# Ink-Schematic.net
KiCad netlist of a schematic drawn in EAGLE
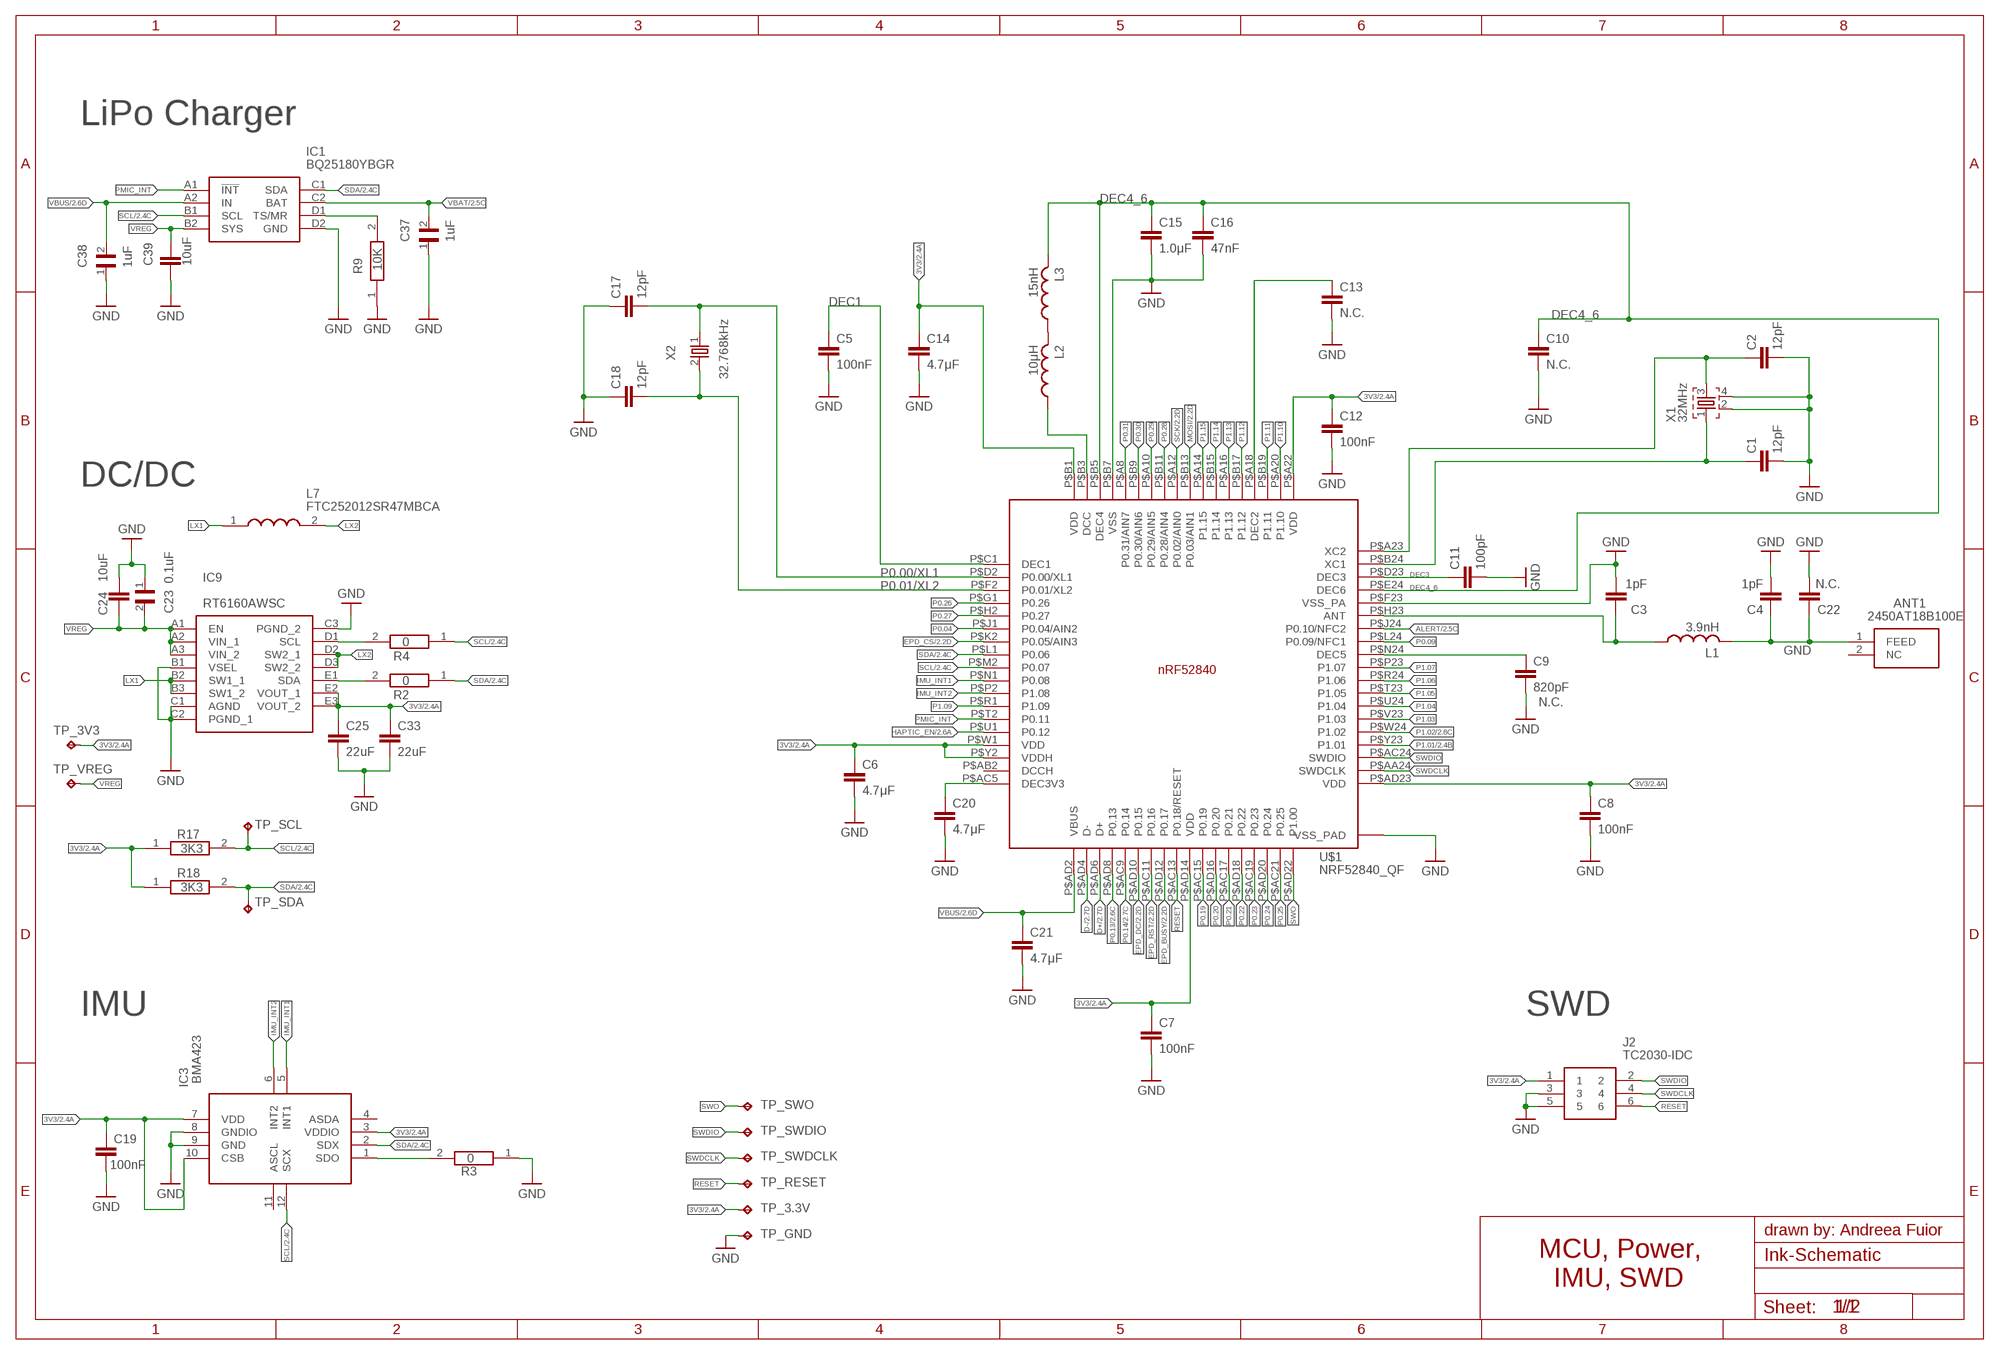
[diagram p0: schematic, sheet 1, part 1 of 2]
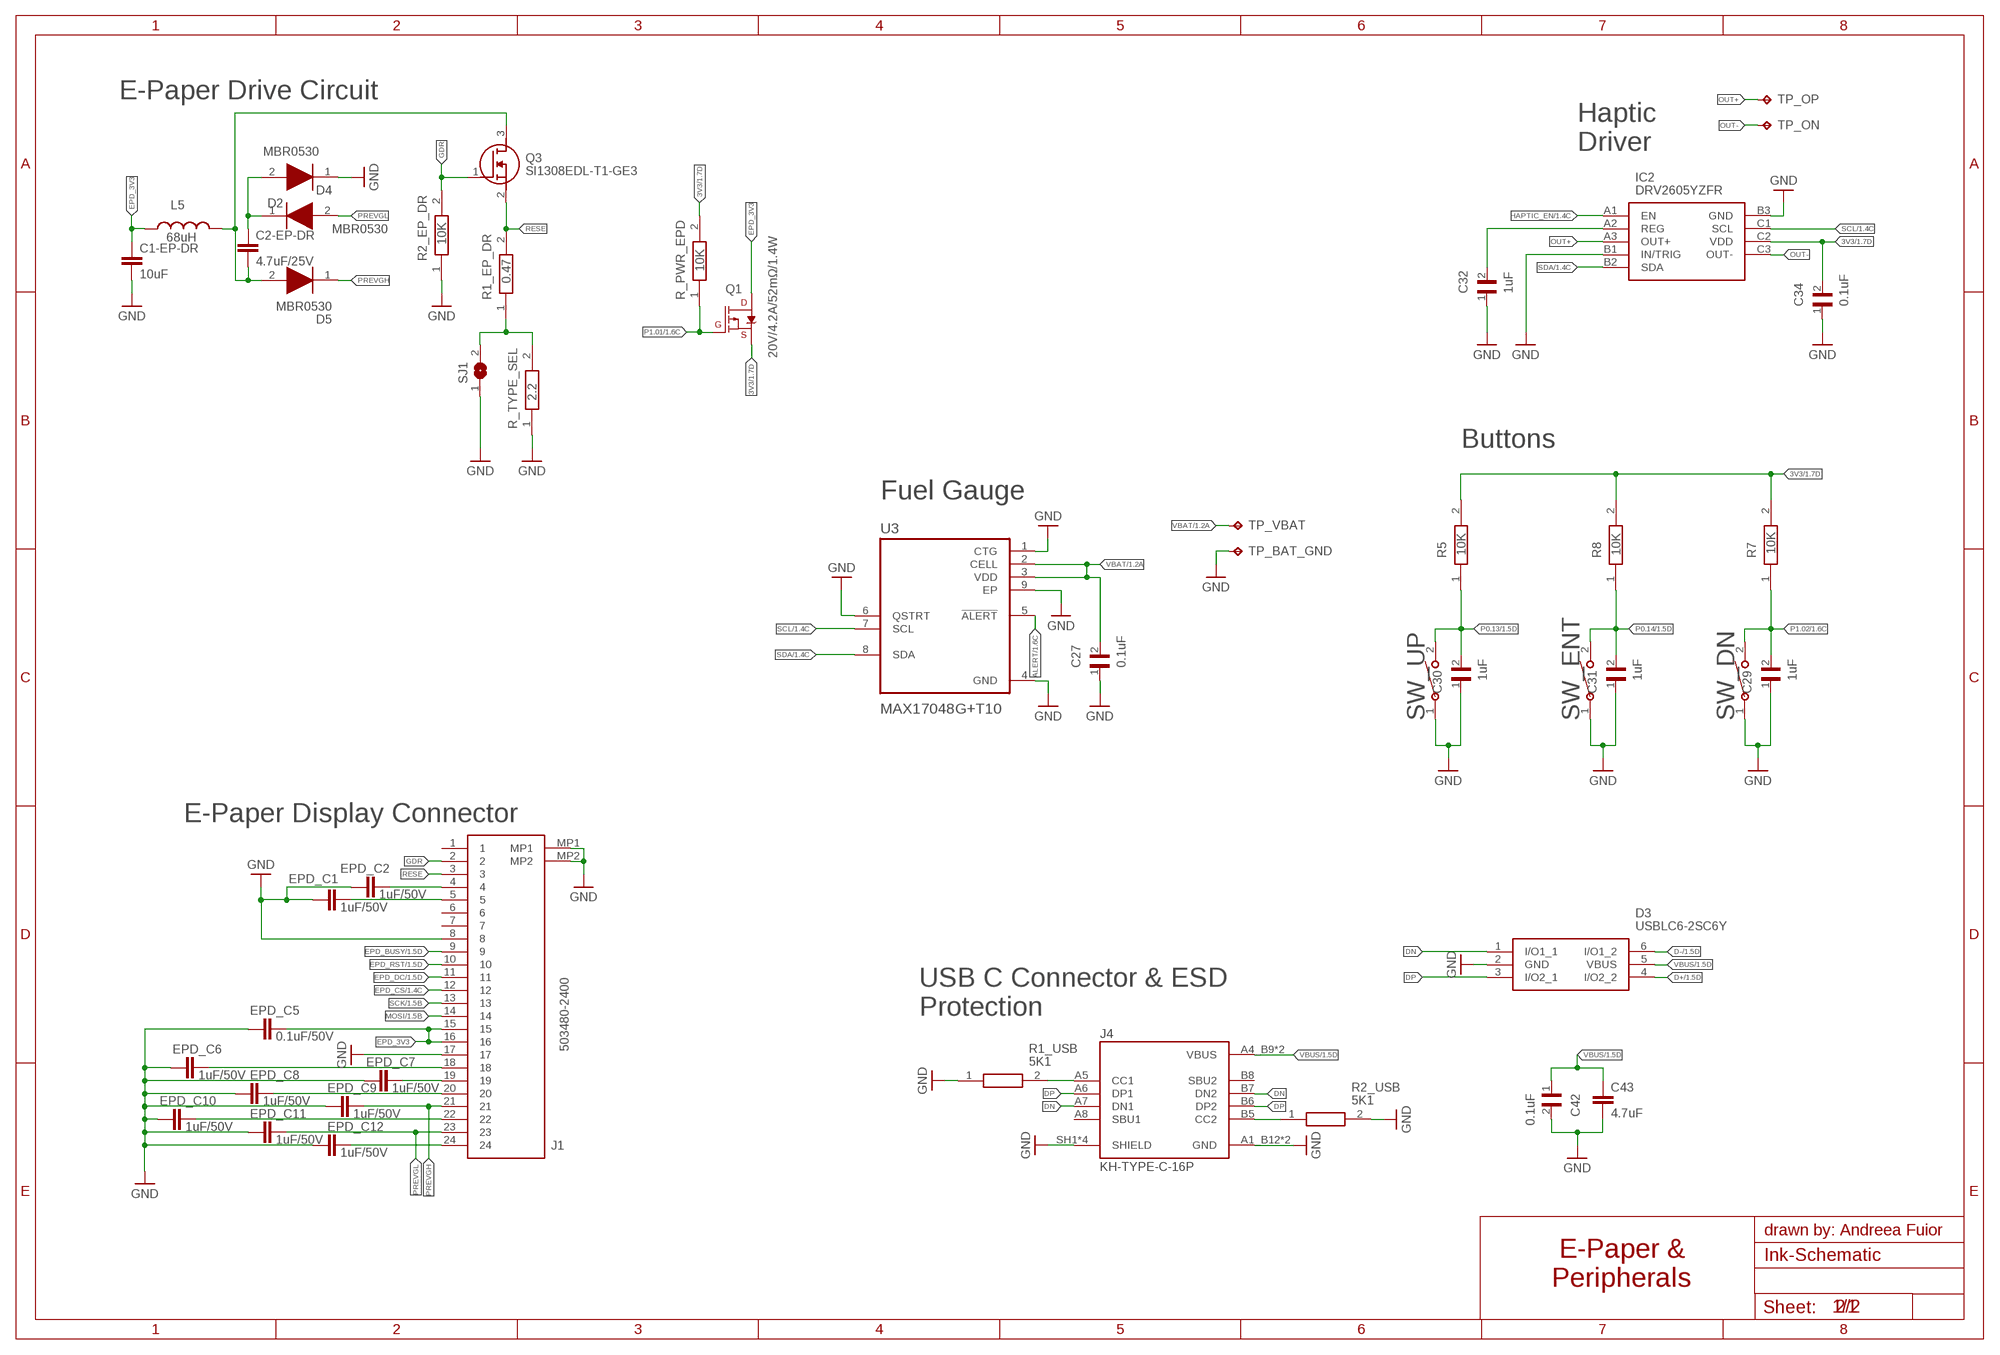
[diagram p1: schematic, sheet 1, part 2 of 2]

(export (version "E")
  (design (tool "Eeschema 10.0.6"))
  (components
    (comp (ref "ANT1")
      (value "2450AT18B100E")
      (footprint "eagle-import:2450AT18B100E_ANTC3216X140N")
      (fields (field (name "MOUSER_PART_NUMBER") "609-2450AT18B100E"))
      (libsource (lib "eagle-import") (part "2450AT18B100E_2450AT18B100E"))
    )
    (comp (ref "C1")
      (value "12pF")
      (footprint "eagle-import:NORDIC_NRF_3_RESC0201_L")
      (libsource (lib "eagle-import") (part "NORDIC_NRF_3_CAPACITOR_0201_L"))
    )
    (comp (ref "C1-EP-DR")
      (value "10uF")
      (footprint "eagle-import:NORDIC_NRF_3_RESC0402_L")
      (libsource (lib "eagle-import") (part "NORDIC_NRF_3_CAPACITOR_0402_L"))
    )
    (comp (ref "C2")
      (value "12pF")
      (footprint "eagle-import:NORDIC_NRF_3_RESC0201_L")
      (libsource (lib "eagle-import") (part "NORDIC_NRF_3_CAPACITOR_0201_L"))
    )
    (comp (ref "C2-EP-DR")
      (value "4.7uF/25V")
      (footprint "eagle-import:NORDIC_NRF_3_RESC0402_L")
      (libsource (lib "eagle-import") (part "NORDIC_NRF_3_CAPACITOR_0402_L"))
    )
    (comp (ref "C3")
      (value "1pF")
      (footprint "eagle-import:NORDIC_NRF_3_RESC0201_L")
      (libsource (lib "eagle-import") (part "NORDIC_NRF_3_CAPACITOR_0201_L"))
    )
    (comp (ref "C4")
      (value "1pF")
      (footprint "eagle-import:NORDIC_NRF_3_RESC0201_L")
      (libsource (lib "eagle-import") (part "NORDIC_NRF_3_CAPACITOR_0201_L"))
    )
    (comp (ref "C5")
      (value "100nF")
      (footprint "eagle-import:NORDIC_NRF_3_RESC0201_L")
      (libsource (lib "eagle-import") (part "NORDIC_NRF_3_CAPACITOR_0201_L"))
    )
    (comp (ref "C6")
      (value "4.7μF")
      (footprint "eagle-import:NORDIC_NRF_3_RESC0402_L")
      (libsource (lib "eagle-import") (part "NORDIC_NRF_3_CAPACITOR_0402_L"))
    )
    (comp (ref "C7")
      (value "100nF")
      (footprint "eagle-import:NORDIC_NRF_3_RESC0201_L")
      (libsource (lib "eagle-import") (part "NORDIC_NRF_3_CAPACITOR_0201_L"))
    )
    (comp (ref "C8")
      (value "100nF")
      (footprint "eagle-import:NORDIC_NRF_3_RESC0201_L")
      (libsource (lib "eagle-import") (part "NORDIC_NRF_3_CAPACITOR_0201_L"))
    )
    (comp (ref "C9")
      (value "820pF")
      (footprint "eagle-import:NORDIC_NRF_3_RESC0201_L")
      (libsource (lib "eagle-import") (part "NORDIC_NRF_3_CAPACITOR_0201_L"))
    )
    (comp (ref "C10")
      (value "N.C.")
      (footprint "eagle-import:NORDIC_NRF_3_RESC0201_L")
      (libsource (lib "eagle-import") (part "NORDIC_NRF_3_CAPACITOR_0201_L"))
    )
    (comp (ref "C11")
      (value "100pF")
      (footprint "eagle-import:NORDIC_NRF_3_RESC0201_L")
      (libsource (lib "eagle-import") (part "NORDIC_NRF_3_CAPACITOR_0201_L"))
    )
    (comp (ref "C12")
      (value "100nF")
      (footprint "eagle-import:NORDIC_NRF_3_RESC0201_L")
      (libsource (lib "eagle-import") (part "NORDIC_NRF_3_CAPACITOR_0201_L"))
    )
    (comp (ref "C13")
      (value "N.C.")
      (footprint "eagle-import:NORDIC_NRF_3_RESC0201_L")
      (libsource (lib "eagle-import") (part "NORDIC_NRF_3_CAPACITOR_0201_L"))
    )
    (comp (ref "C14")
      (value "4.7μF")
      (footprint "eagle-import:NORDIC_NRF_3_RESC0402_L")
      (libsource (lib "eagle-import") (part "NORDIC_NRF_3_CAPACITOR_0402_L"))
    )
    (comp (ref "C15")
      (value "1.0μF")
      (footprint "eagle-import:NORDIC_NRF_3_RESC0402_L")
      (libsource (lib "eagle-import") (part "NORDIC_NRF_3_CAPACITOR_0402_L"))
    )
    (comp (ref "C16")
      (value "47nF")
      (footprint "eagle-import:NORDIC_NRF_3_RESC0201_L")
      (libsource (lib "eagle-import") (part "NORDIC_NRF_3_CAPACITOR_0201_L"))
    )
    (comp (ref "C17")
      (value "12pF")
      (footprint "eagle-import:NORDIC_NRF_3_RESC0201_L")
      (libsource (lib "eagle-import") (part "NORDIC_NRF_3_CAPACITOR_0201_L"))
    )
    (comp (ref "C18")
      (value "12pF")
      (footprint "eagle-import:NORDIC_NRF_3_RESC0201_L")
      (libsource (lib "eagle-import") (part "NORDIC_NRF_3_CAPACITOR_0201_L"))
    )
    (comp (ref "C19")
      (value "100nF")
      (footprint "eagle-import:NORDIC_NRF_3_RESC0201_L")
      (libsource (lib "eagle-import") (part "NORDIC_NRF_3_CAPACITOR_0201_L"))
    )
    (comp (ref "C20")
      (value "4.7μF")
      (footprint "eagle-import:NORDIC_NRF_3_RESC0402_L")
      (libsource (lib "eagle-import") (part "NORDIC_NRF_3_CAPACITOR_0402_L"))
    )
    (comp (ref "C21")
      (value "4.7μF")
      (footprint "eagle-import:NORDIC_NRF_3_RESC0402_L")
      (libsource (lib "eagle-import") (part "NORDIC_NRF_3_CAPACITOR_0402_L"))
    )
    (comp (ref "C22")
      (value "N.C.")
      (footprint "eagle-import:NORDIC_NRF_3_RESC0201_L")
      (libsource (lib "eagle-import") (part "NORDIC_NRF_3_CAPACITOR_0201_L"))
    )
    (comp (ref "C23")
      (value "0.1uF")
      (footprint "eagle-import:GRM011R60J152KE01L_2_CAPC0201X13N")
      (fields (field (name "MF") "Murata") (field (name "MP") "GRM011R60J152KE01L"))
      (libsource (lib "eagle-import") (part "GRM011R60J152KE01L_2_GRM011R60J152KE01L"))
    )
    (comp (ref "C24")
      (value "10uF")
      (footprint "eagle-import:NORDIC_NRF_3_RESC0402_L")
      (libsource (lib "eagle-import") (part "NORDIC_NRF_3_CAPACITOR_0402_L"))
    )
    (comp (ref "C25")
      (value "22uF")
      (footprint "eagle-import:NORDIC_NRF_3_RESC0402_L")
      (libsource (lib "eagle-import") (part "NORDIC_NRF_3_CAPACITOR_0402_L"))
    )
    (comp (ref "C27")
      (value "0.1uF")
      (footprint "eagle-import:GRM011R60J152KE01L_2_CAPC0201X13N")
      (fields (field (name "MF") "Murata") (field (name "MP") "GRM011R60J152KE01L"))
      (libsource (lib "eagle-import") (part "GRM011R60J152KE01L_2_GRM011R60J152KE01L"))
    )
    (comp (ref "C29")
      (value "1uF")
      (footprint "eagle-import:GRM011R60J152KE01L_2_CAPC0201X13N")
      (fields (field (name "MF") "Murata") (field (name "MP") "GRM011R60J152KE01L"))
      (libsource (lib "eagle-import") (part "GRM011R60J152KE01L_2_GRM011R60J152KE01L"))
    )
    (comp (ref "C30")
      (value "1uF")
      (footprint "eagle-import:GRM011R60J152KE01L_2_CAPC0201X13N")
      (fields (field (name "MF") "Murata") (field (name "MP") "GRM011R60J152KE01L"))
      (libsource (lib "eagle-import") (part "GRM011R60J152KE01L_2_GRM011R60J152KE01L"))
    )
    (comp (ref "C31")
      (value "1uF")
      (footprint "eagle-import:GRM011R60J152KE01L_2_CAPC0201X13N")
      (fields (field (name "MF") "Murata") (field (name "MP") "GRM011R60J152KE01L"))
      (libsource (lib "eagle-import") (part "GRM011R60J152KE01L_2_GRM011R60J152KE01L"))
    )
    (comp (ref "C32")
      (value "1uF")
      (footprint "eagle-import:GRM011R60J152KE01L_2_CAPC0201X13N")
      (fields (field (name "MF") "Murata") (field (name "MP") "GRM011R60J152KE01L"))
      (libsource (lib "eagle-import") (part "GRM011R60J152KE01L_2_GRM011R60J152KE01L"))
    )
    (comp (ref "C33")
      (value "22uF")
      (footprint "eagle-import:NORDIC_NRF_3_RESC0402_L")
      (libsource (lib "eagle-import") (part "NORDIC_NRF_3_CAPACITOR_0402_L"))
    )
    (comp (ref "C34")
      (value "0.1uF")
      (footprint "eagle-import:GRM011R60J152KE01L_2_CAPC0201X13N")
      (fields (field (name "MF") "Murata") (field (name "MP") "GRM011R60J152KE01L"))
      (libsource (lib "eagle-import") (part "GRM011R60J152KE01L_2_GRM011R60J152KE01L"))
    )
    (comp (ref "C37")
      (value "1uF")
      (footprint "eagle-import:GRM011R60J152KE01L_2_CAPC0201X13N")
      (fields (field (name "MF") "Murata") (field (name "MP") "GRM011R60J152KE01L"))
      (libsource (lib "eagle-import") (part "GRM011R60J152KE01L_2_GRM011R60J152KE01L"))
    )
    (comp (ref "C38")
      (value "1uF")
      (footprint "eagle-import:GRM011R60J152KE01L_2_CAPC0201X13N")
      (fields (field (name "MF") "Murata") (field (name "MP") "GRM011R60J152KE01L"))
      (libsource (lib "eagle-import") (part "GRM011R60J152KE01L_2_GRM011R60J152KE01L"))
    )
    (comp (ref "C39")
      (value "10uF")
      (footprint "eagle-import:NORDIC_NRF_3_RESC0402_L")
      (libsource (lib "eagle-import") (part "NORDIC_NRF_3_CAPACITOR_0402_L"))
    )
    (comp (ref "C42")
      (value "0.1uF")
      (footprint "eagle-import:GRM011R60J152KE01L_2_CAPC0201X13N")
      (fields (field (name "MF") "Murata") (field (name "MP") "GRM011R60J152KE01L"))
      (libsource (lib "eagle-import") (part "GRM011R60J152KE01L_2_GRM011R60J152KE01L"))
    )
    (comp (ref "C43")
      (value "4.7uF")
      (footprint "eagle-import:NORDIC_NRF_3_RESC0402_L")
      (libsource (lib "eagle-import") (part "NORDIC_NRF_3_CAPACITOR_0402_L"))
    )
    (comp (ref "D2")
      (value "MBR0530")
      (footprint "eagle-import:ESP32_C6_LIBRARY_5_SOD3716X135N")
      (fields (field (name "MF") "ON Semiconductor"))
      (libsource (lib "eagle-import") (part "ESP32_C6_LIBRARY_5_MBR0530"))
    )
    (comp (ref "D3")
      (value "USBLC6-2SC6Y")
      (footprint "eagle-import:ESP32_C6_LIBRARY_3_SOT95P280X145-6N")
      (fields (field (name "MF") "STMicroelectronics"))
      (libsource (lib "eagle-import") (part "ESP32_C6_LIBRARY_3_USBLC6-2SC6Y"))
    )
    (comp (ref "D4")
      (value "MBR0530")
      (footprint "eagle-import:ESP32_C6_LIBRARY_5_SOD3716X135N")
      (fields (field (name "MF") "ON Semiconductor"))
      (libsource (lib "eagle-import") (part "ESP32_C6_LIBRARY_5_MBR0530"))
    )
    (comp (ref "D5")
      (value "MBR0530")
      (footprint "eagle-import:ESP32_C6_LIBRARY_5_SOD3716X135N")
      (fields (field (name "MF") "ON Semiconductor"))
      (libsource (lib "eagle-import") (part "ESP32_C6_LIBRARY_5_MBR0530"))
    )
    (comp (ref "EPD_C1")
      (value "1uF/50V")
      (footprint "eagle-import:NORDIC_NRF_3_RESC0402_L")
      (libsource (lib "eagle-import") (part "NORDIC_NRF_3_CAPACITOR_0402_L"))
    )
    (comp (ref "EPD_C2")
      (value "1uF/50V")
      (footprint "eagle-import:NORDIC_NRF_3_RESC0402_L")
      (libsource (lib "eagle-import") (part "NORDIC_NRF_3_CAPACITOR_0402_L"))
    )
    (comp (ref "EPD_C5")
      (value "0.1uF/50V")
      (footprint "eagle-import:NORDIC_NRF_3_RESC0402_L")
      (libsource (lib "eagle-import") (part "NORDIC_NRF_3_CAPACITOR_0402_L"))
    )
    (comp (ref "EPD_C6")
      (value "1uF/50V")
      (footprint "eagle-import:NORDIC_NRF_3_RESC0402_L")
      (libsource (lib "eagle-import") (part "NORDIC_NRF_3_CAPACITOR_0402_L"))
    )
    (comp (ref "EPD_C7")
      (value "1uF/50V")
      (footprint "eagle-import:NORDIC_NRF_3_RESC0402_L")
      (libsource (lib "eagle-import") (part "NORDIC_NRF_3_CAPACITOR_0402_L"))
    )
    (comp (ref "EPD_C8")
      (value "1uF/50V")
      (footprint "eagle-import:NORDIC_NRF_3_RESC0402_L")
      (libsource (lib "eagle-import") (part "NORDIC_NRF_3_CAPACITOR_0402_L"))
    )
    (comp (ref "EPD_C9")
      (value "1uF/50V")
      (footprint "eagle-import:NORDIC_NRF_3_RESC0402_L")
      (libsource (lib "eagle-import") (part "NORDIC_NRF_3_CAPACITOR_0402_L"))
    )
    (comp (ref "EPD_C10")
      (value "1uF/50V")
      (footprint "eagle-import:NORDIC_NRF_3_RESC0402_L")
      (libsource (lib "eagle-import") (part "NORDIC_NRF_3_CAPACITOR_0402_L"))
    )
    (comp (ref "EPD_C11")
      (value "1uF/50V")
      (footprint "eagle-import:NORDIC_NRF_3_RESC0402_L")
      (libsource (lib "eagle-import") (part "NORDIC_NRF_3_CAPACITOR_0402_L"))
    )
    (comp (ref "EPD_C12")
      (value "1uF/50V")
      (footprint "eagle-import:NORDIC_NRF_3_RESC0402_L")
      (libsource (lib "eagle-import") (part "NORDIC_NRF_3_CAPACITOR_0402_L"))
    )
    (comp (ref "IC1")
      (value "BQ25180YBGR")
      (footprint "eagle-import:BQ25180YBGR_BGA8C40P2X4_100X155X50")
      (fields (field (name "MOUSER_PART_NUMBER") "595-BQ25180YBGR"))
      (libsource (lib "eagle-import") (part "BQ25180YBGR_BQ25180YBGR"))
    )
    (comp (ref "IC2")
      (value "DRV2605YZFR")
      (footprint "eagle-import:DRV2605YZFR_BGA9C50P3X3_144X144X62")
      (libsource (lib "eagle-import") (part "DRV2605YZFR_DRV2605YZFR"))
    )
    (comp (ref "IC3")
      (value "BMA423")
      (footprint "eagle-import:BMA423_BMA423")
      (fields (field (name "MOUSER_PART_NUMBER") "262-BMA423"))
      (libsource (lib "eagle-import") (part "BMA423_BMA423"))
    )
    (comp (ref "IC9")
      (value "RT6160AWSC")
      (footprint "eagle-import:RT6160AWSC_BGA15C40P3X5_140X230X60")
      (fields (field (name "MOUSER_PART_NUMBER") "835-RT6160AWSC"))
      (libsource (lib "eagle-import") (part "RT6160AWSC_RT6160AWSC"))
    )
    (comp (ref "J1")
      (value "503480-2400")
      (footprint "eagle-import:503480-2400_5034802400")
      (fields (field (name "MOUSER_PART_NUMBER") "538-503480-2400"))
      (libsource (lib "eagle-import") (part "503480-2400_503480-2400"))
    )
    (comp (ref "J2")
      (value "TC2030-IDC")
      (footprint "eagle-import:TC2030-IDC_TC2030IDC")
      (libsource (lib "eagle-import") (part "TC2030-IDC_TC2030-IDC"))
    )
    (comp (ref "J4")
      (value "KH-TYPE-C-16P")
      (footprint "eagle-import:KH-TYPE-C-16P_KINGHELM_KH-TYPE-C-16P")
      (fields (field (name "MF") "kinghelm"))
      (libsource (lib "eagle-import") (part "KH-TYPE-C-16P_KH-TYPE-C-16P"))
    )
    (comp (ref "L1")
      (value "3.9nH")
      (footprint "eagle-import:NORDIC_NRF_2_RESC0402_L")
      (libsource (lib "eagle-import") (part "NORDIC_NRF_2_INDUCTOR_0402_L"))
    )
    (comp (ref "L2")
      (value "10μH")
      (footprint "eagle-import:NORDIC_NRF_2_RESC0402_L")
      (libsource (lib "eagle-import") (part "NORDIC_NRF_2_INDUCTOR_0402_L"))
    )
    (comp (ref "L3")
      (value "15nH")
      (footprint "eagle-import:NORDIC_NRF_2_RESC0402_L")
      (libsource (lib "eagle-import") (part "NORDIC_NRF_2_INDUCTOR_0402_L"))
    )
    (comp (ref "L5")
      (value "68uH")
      (footprint "eagle-import:NORDIC_NRF_2_RESC0402_L")
      (libsource (lib "eagle-import") (part "NORDIC_NRF_2_INDUCTOR_0402_L"))
    )
    (comp (ref "L7")
      (value "FTC252012SR47MBCA")
      (footprint "eagle-import:MLP2016SR47MT0S1_INDC2016X100N")
      (libsource (lib "eagle-import") (part "MLP2016SR47MT0S1_FTC252012SR47MBCA"))
    )
    (comp (ref "Q1")
      (value "20V/4.2A/52mΩ/1.4W")
      (footprint "eagle-import:ESP32_C6_LIBRARY_4_ESP32_C6_LIBRARY_4_ESP32_C6_LIBRARY_4_ESP32_C6_LIBRARY_4_ESP32_WROVER_SPARKFUN-DISCRETESEMI_SOT23-3")
      (libsource (lib "eagle-import") (part "ESP32_C6_LIBRARY_4_ESP32_WROVER_SPARKFUN-DISCRETESEMI_MOSFET_PCH-DMG2305UX-7"))
    )
    (comp (ref "Q3")
      (value "SI1308EDL-T1-GE3")
      (footprint "eagle-import:ESP32_C6_LIBRARY_6_SOT65P210X110-3N")
      (fields (field (name "MF") "Vishay Siliconix"))
      (libsource (lib "eagle-import") (part "ESP32_C6_LIBRARY_6_SI1308EDL-T1-GE3"))
    )
    (comp (ref "R1_EP_DR")
      (value "0.47")
      (footprint "eagle-import:CPF0201D7K68C1_0201")
      (libsource (lib "eagle-import") (part "CPF0201D7K68C1_CPF0201D7K68C1"))
    )
    (comp (ref "R1_USB")
      (value "5K1")
      (footprint "eagle-import:CPF0201D7K68C1_0201")
      (libsource (lib "eagle-import") (part "CPF0201D7K68C1_CPF0201D7K68C1"))
    )
    (comp (ref "R2")
      (value "0")
      (footprint "eagle-import:CPF0201D7K68C1_0201")
      (libsource (lib "eagle-import") (part "CPF0201D7K68C1_CPF0201D7K68C1"))
    )
    (comp (ref "R2_EP_DR")
      (value "10K")
      (footprint "eagle-import:CPF0201D7K68C1_0201")
      (libsource (lib "eagle-import") (part "CPF0201D7K68C1_CPF0201D7K68C1"))
    )
    (comp (ref "R2_USB")
      (value "5K1")
      (footprint "eagle-import:CPF0201D7K68C1_0201")
      (libsource (lib "eagle-import") (part "CPF0201D7K68C1_CPF0201D7K68C1"))
    )
    (comp (ref "R3")
      (value "0")
      (footprint "eagle-import:CPF0201D7K68C1_0201")
      (libsource (lib "eagle-import") (part "CPF0201D7K68C1_CPF0201D7K68C1"))
    )
    (comp (ref "R4")
      (value "0")
      (footprint "eagle-import:CPF0201D7K68C1_0201")
      (libsource (lib "eagle-import") (part "CPF0201D7K68C1_CPF0201D7K68C1"))
    )
    (comp (ref "R5")
      (value "10K")
      (footprint "eagle-import:CPF0201D7K68C1_0201")
      (libsource (lib "eagle-import") (part "CPF0201D7K68C1_CPF0201D7K68C1"))
    )
    (comp (ref "R7")
      (value "10K")
      (footprint "eagle-import:CPF0201D7K68C1_0201")
      (libsource (lib "eagle-import") (part "CPF0201D7K68C1_CPF0201D7K68C1"))
    )
    (comp (ref "R8")
      (value "10K")
      (footprint "eagle-import:CPF0201D7K68C1_0201")
      (libsource (lib "eagle-import") (part "CPF0201D7K68C1_CPF0201D7K68C1"))
    )
    (comp (ref "R9")
      (value "10K")
      (footprint "eagle-import:CPF0201D7K68C1_0201")
      (libsource (lib "eagle-import") (part "CPF0201D7K68C1_CPF0201D7K68C1"))
    )
    (comp (ref "R17")
      (value "3K3")
      (footprint "eagle-import:CPF0201D7K68C1_0201")
      (libsource (lib "eagle-import") (part "CPF0201D7K68C1_CPF0201D7K68C1"))
    )
    (comp (ref "R18")
      (value "3K3")
      (footprint "eagle-import:CPF0201D7K68C1_0201")
      (libsource (lib "eagle-import") (part "CPF0201D7K68C1_CPF0201D7K68C1"))
    )
    (comp (ref "R_PWR_EPD")
      (value "10K")
      (footprint "eagle-import:CPF0201D7K68C1_0201")
      (libsource (lib "eagle-import") (part "CPF0201D7K68C1_CPF0201D7K68C1"))
    )
    (comp (ref "R_TYPE_SEL")
      (value "2.2")
      (footprint "eagle-import:CPF0201D7K68C1_0201")
      (libsource (lib "eagle-import") (part "CPF0201D7K68C1_CPF0201D7K68C1"))
    )
    (comp (ref "SJ1")
      (value "ESP32_C6_LIBRARY_7_JUMPER_SJ")
      (footprint "eagle-import:ESP32_C6_LIBRARY_7_JUMPER_SJ")
      (libsource (lib "eagle-import") (part "ESP32_C6_LIBRARY_7_JUMPER_SJ"))
    )
    (comp (ref "SW_DN")
      (value "2025-10-22_07-23-44_LIBRARY_EVP-AKE31ASW_EVP-AKE31A_PAN")
      (footprint "eagle-import:2025-10-22_07-23-44_LIBRARY_SW_EVP-AKE31A_PAN")
      (fields
        (field (name "MANUFACTURER_PART_NUMBER") "EVP-AKE31A")
        (field (name "COPYRIGHT") "Copyright (C) 2025 Ultra Librarian. All rights reserved.")
      )
      (libsource (lib "eagle-import") (part "2025-10-22_07-23-44_LIBRARY_EVP-AKE31ASW_EVP-AKE31A_PAN"))
    )
    (comp (ref "SW_ENT")
      (value "2025-10-22_07-23-44_LIBRARY_EVP-AKE31ASW_EVP-AKE31A_PAN")
      (footprint "eagle-import:2025-10-22_07-23-44_LIBRARY_SW_EVP-AKE31A_PAN")
      (fields
        (field (name "MANUFACTURER_PART_NUMBER") "EVP-AKE31A")
        (field (name "COPYRIGHT") "Copyright (C) 2025 Ultra Librarian. All rights reserved.")
      )
      (libsource (lib "eagle-import") (part "2025-10-22_07-23-44_LIBRARY_EVP-AKE31ASW_EVP-AKE31A_PAN"))
    )
    (comp (ref "SW_UP")
      (value "2025-10-22_07-23-44_LIBRARY_EVP-AKE31ASW_EVP-AKE31A_PAN")
      (footprint "eagle-import:2025-10-22_07-23-44_LIBRARY_SW_EVP-AKE31A_PAN")
      (fields
        (field (name "MANUFACTURER_PART_NUMBER") "EVP-AKE31A")
        (field (name "COPYRIGHT") "Copyright (C) 2025 Ultra Librarian. All rights reserved.")
      )
      (libsource (lib "eagle-import") (part "2025-10-22_07-23-44_LIBRARY_EVP-AKE31ASW_EVP-AKE31A_PAN"))
    )
    (comp (ref "TP_3.3V")
      (value "HECTOR_WATCH_1_TPTP20R")
      (footprint "eagle-import:HECTOR_WATCH_1_TP20R")
      (libsource (lib "eagle-import") (part "HECTOR_WATCH_1_TPTP20R"))
    )
    (comp (ref "TP_3V3")
      (value "HECTOR_WATCH_1_TPTP20R")
      (footprint "eagle-import:HECTOR_WATCH_1_TP20R")
      (libsource (lib "eagle-import") (part "HECTOR_WATCH_1_TPTP20R"))
    )
    (comp (ref "TP_BAT_GND")
      (value "HECTOR_WATCH_1_TPTP20R")
      (footprint "eagle-import:HECTOR_WATCH_1_TP20R")
      (libsource (lib "eagle-import") (part "HECTOR_WATCH_1_TPTP20R"))
    )
    (comp (ref "TP_GND")
      (value "HECTOR_WATCH_1_TPTP20R")
      (footprint "eagle-import:HECTOR_WATCH_1_TP20R")
      (libsource (lib "eagle-import") (part "HECTOR_WATCH_1_TPTP20R"))
    )
    (comp (ref "TP_ON")
      (value "HECTOR_WATCH_1_TPTP20R")
      (footprint "eagle-import:HECTOR_WATCH_1_TP20R")
      (libsource (lib "eagle-import") (part "HECTOR_WATCH_1_TPTP20R"))
    )
    (comp (ref "TP_OP")
      (value "HECTOR_WATCH_1_TPTP20R")
      (footprint "eagle-import:HECTOR_WATCH_1_TP20R")
      (libsource (lib "eagle-import") (part "HECTOR_WATCH_1_TPTP20R"))
    )
    (comp (ref "TP_RESET")
      (value "HECTOR_WATCH_1_TPTP20R")
      (footprint "eagle-import:HECTOR_WATCH_1_TP20R")
      (libsource (lib "eagle-import") (part "HECTOR_WATCH_1_TPTP20R"))
    )
    (comp (ref "TP_SCL")
      (value "HECTOR_WATCH_1_TPTP20R")
      (footprint "eagle-import:HECTOR_WATCH_1_TP20R")
      (libsource (lib "eagle-import") (part "HECTOR_WATCH_1_TPTP20R"))
    )
    (comp (ref "TP_SDA")
      (value "HECTOR_WATCH_1_TPTP20R")
      (footprint "eagle-import:HECTOR_WATCH_1_TP20R")
      (libsource (lib "eagle-import") (part "HECTOR_WATCH_1_TPTP20R"))
    )
    (comp (ref "TP_SWDCLK")
      (value "HECTOR_WATCH_1_TPTP20R")
      (footprint "eagle-import:HECTOR_WATCH_1_TP20R")
      (libsource (lib "eagle-import") (part "HECTOR_WATCH_1_TPTP20R"))
    )
    (comp (ref "TP_SWDIO")
      (value "HECTOR_WATCH_1_TPTP20R")
      (footprint "eagle-import:HECTOR_WATCH_1_TP20R")
      (libsource (lib "eagle-import") (part "HECTOR_WATCH_1_TPTP20R"))
    )
    (comp (ref "TP_SWO")
      (value "HECTOR_WATCH_1_TPTP20R")
      (footprint "eagle-import:HECTOR_WATCH_1_TP20R")
      (libsource (lib "eagle-import") (part "HECTOR_WATCH_1_TPTP20R"))
    )
    (comp (ref "TP_VBAT")
      (value "HECTOR_WATCH_1_TPTP20R")
      (footprint "eagle-import:HECTOR_WATCH_1_TP20R")
      (libsource (lib "eagle-import") (part "HECTOR_WATCH_1_TPTP20R"))
    )
    (comp (ref "TP_VREG")
      (value "HECTOR_WATCH_1_TPTP20R")
      (footprint "eagle-import:HECTOR_WATCH_1_TP20R")
      (libsource (lib "eagle-import") (part "HECTOR_WATCH_1_TPTP20R"))
    )
    (comp (ref "U$1")
      (value "NRF52840_QF")
      (footprint "eagle-import:NORDIC_NRF_4_AQFN50P700X700X85_HS-74N")
      (libsource (lib "eagle-import") (part "NORDIC_NRF_4_NRF52840_QF"))
    )
    (comp (ref "U3")
      (value "MAX17048G+T10")
      (footprint "eagle-import:ESP32_C6_LIBRARY_SON50P200X200X80-9N")
      (fields (field (name "MF") "Analog Devices"))
      (libsource (lib "eagle-import") (part "ESP32_C6_LIBRARY_MAX17048G+T10"))
    )
    (comp (ref "X1")
      (value "32MHz")
      (footprint "eagle-import:NORDIC_NRF_BT-XTAL_2016_N")
      (libsource (lib "eagle-import") (part "NORDIC_NRF_XTAL_32MHZ"))
    )
    (comp (ref "X2")
      (value "32.768kHz")
      (footprint "eagle-import:NORDIC_NRF_1_XTAL_3215_N")
      (libsource (lib "eagle-import") (part "NORDIC_NRF_1_XTAL_32KHZ"))
    )
  )
  (nets
    (net (code "1") (name "/DEC1") (class "Default")
      (node (ref "C5") (pin "1") (pinfunction "1_1") (pintype "passive"))
      (node (ref "U$1") (pin "P$C1") (pinfunction "DEC1_P$C1") (pintype "power_in"))
    )
    (net (code "2") (name "/DEC3") (class "Default")
      (node (ref "C11") (pin "1") (pinfunction "1_1") (pintype "passive"))
      (node (ref "U$1") (pin "P$D23") (pinfunction "DEC3_P$D23") (pintype "bidirectional"))
    )
    (net (code "3") (name "/DEC4_6") (class "Default")
      (node (ref "C10") (pin "1") (pinfunction "1_1") (pintype "passive"))
      (node (ref "C15") (pin "1") (pinfunction "1_1") (pintype "passive"))
      (node (ref "C16") (pin "1") (pinfunction "1_1") (pintype "passive"))
      (node (ref "L3") (pin "2") (pinfunction "2_2") (pintype "passive"))
      (node (ref "U$1") (pin "P$B5") (pinfunction "DEC4_P$B5") (pintype "power_in"))
      (node (ref "U$1") (pin "P$E24") (pinfunction "DEC6_P$E24") (pintype "bidirectional"))
    )
    (net (code "4") (name "/P0.00{slash}XL1") (class "Default")
      (node (ref "C17") (pin "2") (pinfunction "2_2") (pintype "passive"))
      (node (ref "U$1") (pin "P$D2") (pinfunction "P0.00/XL1_P$D2") (pintype "bidirectional"))
      (node (ref "X2") (pin "1") (pinfunction "1_1") (pintype "passive"))
    )
    (net (code "5") (name "/P0.01{slash}XL2") (class "Default")
      (node (ref "C18") (pin "2") (pinfunction "2_2") (pintype "passive"))
      (node (ref "U$1") (pin "P$F2") (pinfunction "P0.01/XL2_P$F2") (pintype "bidirectional"))
      (node (ref "X2") (pin "2") (pinfunction "2_2") (pintype "passive"))
    )
    (net (code "6") (name "3V3{slash}1.7D") (class "Default")
      (node (ref "C34") (pin "2") (pinfunction "2_2") (pintype "passive"))
      (node (ref "IC2") (pin "C2") (pinfunction "VDD_C2") (pintype "bidirectional"))
      (node (ref "Q1") (pin "2") (pinfunction "S_2") (pintype "bidirectional"))
      (node (ref "R5") (pin "2") (pinfunction "2_2") (pintype "bidirectional"))
      (node (ref "R7") (pin "2") (pinfunction "2_2") (pintype "bidirectional"))
      (node (ref "R8") (pin "2") (pinfunction "2_2") (pintype "bidirectional"))
      (node (ref "R_PWR_EPD") (pin "2") (pinfunction "2_2") (pintype "bidirectional"))
    )
    (net (code "7") (name "3V3{slash}2.4A") (class "Default")
      (node (ref "C12") (pin "1") (pinfunction "1_1") (pintype "passive"))
      (node (ref "C14") (pin "1") (pinfunction "1_1") (pintype "passive"))
      (node (ref "C19") (pin "1") (pinfunction "1_1") (pintype "passive"))
      (node (ref "C25") (pin "1") (pinfunction "1_1") (pintype "passive"))
      (node (ref "C33") (pin "1") (pinfunction "1_1") (pintype "passive"))
      (node (ref "C6") (pin "1") (pinfunction "1_1") (pintype "passive"))
      (node (ref "C7") (pin "1") (pinfunction "1_1") (pintype "passive"))
      (node (ref "C8") (pin "1") (pinfunction "1_1") (pintype "passive"))
      (node (ref "IC3") (pin "10") (pinfunction "CSB_10") (pintype "bidirectional"))
      (node (ref "IC3") (pin "3") (pinfunction "VDDIO_3") (pintype "bidirectional"))
      (node (ref "IC3") (pin "7") (pinfunction "VDD_7") (pintype "bidirectional"))
      (node (ref "IC9") (pin "E2") (pinfunction "VOUT_1_E2") (pintype "bidirectional"))
      (node (ref "IC9") (pin "E3") (pinfunction "VOUT_2_E3") (pintype "bidirectional"))
      (node (ref "J2") (pin "1") (pinfunction "1_1") (pintype "bidirectional"))
      (node (ref "R17") (pin "1") (pinfunction "1_1") (pintype "bidirectional"))
      (node (ref "R18") (pin "1") (pinfunction "1_1") (pintype "bidirectional"))
      (node (ref "TP_3.3V") (pin "TP") (pinfunction "TP_TP") (pintype "input"))
      (node (ref "TP_3V3") (pin "TP") (pinfunction "TP_TP") (pintype "input"))
      (node (ref "U$1") (pin "P$A22") (pinfunction "VDD_P$A22") (pintype "power_in"))
      (node (ref "U$1") (pin "P$AD14") (pinfunction "VDD_P$AD14") (pintype "power_in"))
      (node (ref "U$1") (pin "P$AD23") (pinfunction "VDD_P$AD23") (pintype "power_in"))
      (node (ref "U$1") (pin "P$B1") (pinfunction "VDD_P$B1") (pintype "power_in"))
      (node (ref "U$1") (pin "P$W1") (pinfunction "VDD_P$W1") (pintype "power_in"))
      (node (ref "U$1") (pin "P$Y2") (pinfunction "VDDH_P$Y2") (pintype "power_in"))
    )
    (net (code "8") (name "ALERT{slash}1.6C") (class "Default")
      (node (ref "U3") (pin "5") (pinfunction "~{ALERT}_5") (pintype "output"))
    )
    (net (code "9") (name "ALERT{slash}2.5C") (class "Default")
      (node (ref "U$1") (pin "P$J24") (pinfunction "P0.10/NFC2_P$J24") (pintype "bidirectional"))
    )
    (net (code "10") (name "D+{slash}1.5D") (class "Default")
      (node (ref "D3") (pin "4") (pinfunction "I/O2_2_4") (pintype "bidirectional"))
    )
    (net (code "11") (name "D+{slash}2.7D") (class "Default")
      (node (ref "U$1") (pin "P$AD6") (pinfunction "D+_P$AD6") (pintype "bidirectional"))
    )
    (net (code "12") (name "D-{slash}1.5D") (class "Default")
      (node (ref "D3") (pin "6") (pinfunction "I/O1_2_6") (pintype "bidirectional"))
    )
    (net (code "13") (name "D-{slash}2.7D") (class "Default")
      (node (ref "U$1") (pin "P$AD4") (pinfunction "D-_P$AD4") (pintype "bidirectional"))
    )
    (net (code "14") (name "DN") (class "Default")
      (node (ref "D3") (pin "1") (pinfunction "I/O1_1_1") (pintype "bidirectional"))
      (node (ref "J4") (pin "A7") (pinfunction "DN1_A7") (pintype "bidirectional"))
      (node (ref "J4") (pin "B7") (pinfunction "DN2_B7") (pintype "bidirectional"))
    )
    (net (code "15") (name "DP") (class "Default")
      (node (ref "D3") (pin "3") (pinfunction "I/O2_1_3") (pintype "bidirectional"))
      (node (ref "J4") (pin "A6") (pinfunction "DP1_A6") (pintype "bidirectional"))
      (node (ref "J4") (pin "B6") (pinfunction "DP2_B6") (pintype "bidirectional"))
    )
    (net (code "16") (name "EPD_3V3") (class "Default")
      (node (ref "C1-EP-DR") (pin "1") (pinfunction "1_1") (pintype "passive"))
      (node (ref "EPD_C5") (pin "1") (pinfunction "1_1") (pintype "passive"))
      (node (ref "J1") (pin "15") (pinfunction "15_15") (pintype "bidirectional"))
      (node (ref "J1") (pin "16") (pinfunction "16_16") (pintype "bidirectional"))
      (node (ref "L5") (pin "1") (pinfunction "1_1") (pintype "passive"))
      (node (ref "Q1") (pin "3") (pinfunction "D_3") (pintype "bidirectional"))
    )
    (net (code "17") (name "EPD_BUSY{slash}1.5D") (class "Default")
      (node (ref "J1") (pin "9") (pinfunction "9_9") (pintype "bidirectional"))
    )
    (net (code "18") (name "EPD_BUSY{slash}2.2D") (class "Default")
      (node (ref "U$1") (pin "P$AD12") (pinfunction "P0.17_P$AD12") (pintype "bidirectional"))
    )
    (net (code "19") (name "EPD_CS{slash}1.4C") (class "Default")
      (node (ref "J1") (pin "12") (pinfunction "12_12") (pintype "bidirectional"))
    )
    (net (code "20") (name "EPD_CS{slash}2.2D") (class "Default")
      (node (ref "U$1") (pin "P$K2") (pinfunction "P0.05/AIN3_P$K2") (pintype "bidirectional"))
    )
    (net (code "21") (name "EPD_DC{slash}1.5D") (class "Default")
      (node (ref "J1") (pin "11") (pinfunction "11_11") (pintype "bidirectional"))
    )
    (net (code "22") (name "EPD_DC{slash}2.2D") (class "Default")
      (node (ref "U$1") (pin "P$AD10") (pinfunction "P0.15_P$AD10") (pintype "bidirectional"))
    )
    (net (code "23") (name "EPD_RST{slash}1.5D") (class "Default")
      (node (ref "J1") (pin "10") (pinfunction "10_10") (pintype "bidirectional"))
    )
    (net (code "24") (name "EPD_RST{slash}2.2D") (class "Default")
      (node (ref "U$1") (pin "P$AC11") (pinfunction "P0.16_P$AC11") (pintype "bidirectional"))
    )
    (net (code "25") (name "GDR") (class "Default")
      (node (ref "J1") (pin "2") (pinfunction "2_2") (pintype "bidirectional"))
      (node (ref "Q3") (pin "1") (pinfunction "G_1") (pintype "bidirectional"))
      (node (ref "R2_EP_DR") (pin "2") (pinfunction "2_2") (pintype "bidirectional"))
    )
    (net (code "26") (name "GND") (class "Default")
      (node (ref "ANT1") (pin "1") (pinfunction "FEED_1") (pintype "input"))
      (node (ref "C1") (pin "2") (pinfunction "2_2") (pintype "passive"))
      (node (ref "C1-EP-DR") (pin "2") (pinfunction "2_2") (pintype "passive"))
      (node (ref "C10") (pin "2") (pinfunction "2_2") (pintype "passive"))
      (node (ref "C11") (pin "2") (pinfunction "2_2") (pintype "passive"))
      (node (ref "C12") (pin "2") (pinfunction "2_2") (pintype "passive"))
      (node (ref "C13") (pin "2") (pinfunction "2_2") (pintype "passive"))
      (node (ref "C14") (pin "2") (pinfunction "2_2") (pintype "passive"))
      (node (ref "C15") (pin "2") (pinfunction "2_2") (pintype "passive"))
      (node (ref "C16") (pin "2") (pinfunction "2_2") (pintype "passive"))
      (node (ref "C17") (pin "1") (pinfunction "1_1") (pintype "passive"))
      (node (ref "C18") (pin "1") (pinfunction "1_1") (pintype "passive"))
      (node (ref "C19") (pin "2") (pinfunction "2_2") (pintype "passive"))
      (node (ref "C2") (pin "2") (pinfunction "2_2") (pintype "passive"))
      (node (ref "C20") (pin "2") (pinfunction "2_2") (pintype "passive"))
      (node (ref "C21") (pin "2") (pinfunction "2_2") (pintype "passive"))
      (node (ref "C22") (pin "1") (pinfunction "1_1") (pintype "passive"))
      (node (ref "C22") (pin "2") (pinfunction "2_2") (pintype "passive"))
      (node (ref "C23") (pin "1") (pinfunction "1_1") (pintype "passive"))
      (node (ref "C24") (pin "2") (pinfunction "2_2") (pintype "passive"))
      (node (ref "C25") (pin "2") (pinfunction "2_2") (pintype "passive"))
      (node (ref "C27") (pin "1") (pinfunction "1_1") (pintype "passive"))
      (node (ref "C29") (pin "1") (pinfunction "1_1") (pintype "passive"))
      (node (ref "C3") (pin "2") (pinfunction "2_2") (pintype "passive"))
      (node (ref "C30") (pin "1") (pinfunction "1_1") (pintype "passive"))
      (node (ref "C31") (pin "1") (pinfunction "1_1") (pintype "passive"))
      (node (ref "C32") (pin "1") (pinfunction "1_1") (pintype "passive"))
      (node (ref "C33") (pin "2") (pinfunction "2_2") (pintype "passive"))
      (node (ref "C34") (pin "1") (pinfunction "1_1") (pintype "passive"))
      (node (ref "C37") (pin "1") (pinfunction "1_1") (pintype "passive"))
      (node (ref "C38") (pin "1") (pinfunction "1_1") (pintype "passive"))
      (node (ref "C39") (pin "2") (pinfunction "2_2") (pintype "passive"))
      (node (ref "C4") (pin "1") (pinfunction "1_1") (pintype "passive"))
      (node (ref "C4") (pin "2") (pinfunction "2_2") (pintype "passive"))
      (node (ref "C42") (pin "2") (pinfunction "2_2") (pintype "passive"))
      (node (ref "C43") (pin "2") (pinfunction "2_2") (pintype "passive"))
      (node (ref "C5") (pin "2") (pinfunction "2_2") (pintype "passive"))
      (node (ref "C6") (pin "2") (pinfunction "2_2") (pintype "passive"))
      (node (ref "C7") (pin "2") (pinfunction "2_2") (pintype "passive"))
      (node (ref "C8") (pin "2") (pinfunction "2_2") (pintype "passive"))
      (node (ref "C9") (pin "2") (pinfunction "2_2") (pintype "passive"))
      (node (ref "D3") (pin "2") (pinfunction "GND_2") (pintype "bidirectional"))
      (node (ref "D4") (pin "1") (pinfunction "K_1") (pintype "bidirectional"))
      (node (ref "EPD_C1") (pin "2") (pinfunction "2_2") (pintype "passive"))
      (node (ref "EPD_C10") (pin "2") (pinfunction "2_2") (pintype "passive"))
      (node (ref "EPD_C11") (pin "2") (pinfunction "2_2") (pintype "passive"))
      (node (ref "EPD_C12") (pin "2") (pinfunction "2_2") (pintype "passive"))
      (node (ref "EPD_C2") (pin "2") (pinfunction "2_2") (pintype "passive"))
      (node (ref "EPD_C5") (pin "2") (pinfunction "2_2") (pintype "passive"))
      (node (ref "EPD_C6") (pin "2") (pinfunction "2_2") (pintype "passive"))
      (node (ref "EPD_C7") (pin "2") (pinfunction "2_2") (pintype "passive"))
      (node (ref "EPD_C8") (pin "2") (pinfunction "2_2") (pintype "passive"))
      (node (ref "EPD_C9") (pin "2") (pinfunction "2_2") (pintype "passive"))
      (node (ref "IC1") (pin "D2") (pinfunction "GND_D2") (pintype "bidirectional"))
      (node (ref "IC2") (pin "B1") (pinfunction "IN/TRIG_B1") (pintype "bidirectional"))
      (node (ref "IC2") (pin "B3") (pinfunction "GND_B3") (pintype "bidirectional"))
      (node (ref "IC3") (pin "8") (pinfunction "GNDIO_8") (pintype "bidirectional"))
      (node (ref "IC3") (pin "9") (pinfunction "GND_9") (pintype "bidirectional"))
      (node (ref "IC9") (pin "B1") (pinfunction "VSEL_B1") (pintype "bidirectional"))
      (node (ref "IC9") (pin "C1") (pinfunction "AGND_C1") (pintype "bidirectional"))
      (node (ref "IC9") (pin "C2") (pinfunction "PGND_1_C2") (pintype "bidirectional"))
      (node (ref "IC9") (pin "C3") (pinfunction "PGND_2_C3") (pintype "bidirectional"))
      (node (ref "J1") (pin "17") (pinfunction "17_17") (pintype "bidirectional"))
      (node (ref "J1") (pin "8") (pinfunction "8_8") (pintype "bidirectional"))
      (node (ref "J1") (pin "MP1") (pinfunction "MP1_MP1") (pintype "bidirectional"))
      (node (ref "J1") (pin "MP2") (pinfunction "MP2_MP2") (pintype "bidirectional"))
      (node (ref "J2") (pin "3") (pinfunction "3_3") (pintype "bidirectional"))
      (node (ref "J2") (pin "5") (pinfunction "5_5") (pintype "bidirectional"))
      (node (ref "J4") (pin "A12_B1") (pinfunction "GND_A12_B1") (pintype "power_in"))
      (node (ref "J4") (pin "A1_B12") (pinfunction "GND_A1_B12") (pintype "power_in"))
      (node (ref "J4") (pin "SH1") (pinfunction "SHIELD_SH1") (pintype "passive"))
      (node (ref "J4") (pin "SH2") (pinfunction "SHIELD_SH2") (pintype "passive"))
      (node (ref "J4") (pin "SH3") (pinfunction "SHIELD_SH3") (pintype "passive"))
      (node (ref "J4") (pin "SH4") (pinfunction "SHIELD_SH4") (pintype "passive"))
      (node (ref "L1") (pin "2") (pinfunction "2_2") (pintype "passive"))
      (node (ref "R1_USB") (pin "1") (pinfunction "1_1") (pintype "bidirectional"))
      (node (ref "R2_EP_DR") (pin "1") (pinfunction "1_1") (pintype "bidirectional"))
      (node (ref "R2_USB") (pin "2") (pinfunction "2_2") (pintype "bidirectional"))
      (node (ref "R3") (pin "1") (pinfunction "1_1") (pintype "bidirectional"))
      (node (ref "R9") (pin "1") (pinfunction "1_1") (pintype "bidirectional"))
      (node (ref "R_TYPE_SEL") (pin "1") (pinfunction "1_1") (pintype "bidirectional"))
      (node (ref "SJ1") (pin "1") (pinfunction "1_1") (pintype "passive"))
      (node (ref "SW_DN") (pin "1") (pinfunction "1_1") (pintype "passive"))
      (node (ref "SW_ENT") (pin "1") (pinfunction "1_1") (pintype "passive"))
      (node (ref "SW_UP") (pin "1") (pinfunction "1_1") (pintype "passive"))
      (node (ref "TP_BAT_GND") (pin "TP") (pinfunction "TP_TP") (pintype "input"))
      (node (ref "TP_GND") (pin "TP") (pinfunction "TP_TP") (pintype "input"))
      (node (ref "U$1") (pin "P$74") (pinfunction "VSS_PAD_P$74") (pintype "bidirectional"))
      (node (ref "U$1") (pin "P$75") (pinfunction "VSS_PAD_P$75") (pintype "bidirectional"))
      (node (ref "U$1") (pin "P$76") (pinfunction "VSS_PAD_P$76") (pintype "bidirectional"))
      (node (ref "U$1") (pin "P$77") (pinfunction "VSS_PAD_P$77") (pintype "bidirectional"))
      (node (ref "U$1") (pin "P$78") (pinfunction "VSS_PAD_P$78") (pintype "bidirectional"))
      (node (ref "U$1") (pin "P$79") (pinfunction "VSS_PAD_P$79") (pintype "bidirectional"))
      (node (ref "U$1") (pin "P$80") (pinfunction "VSS_PAD_P$80") (pintype "bidirectional"))
      (node (ref "U$1") (pin "P$81") (pinfunction "VSS_PAD_P$81") (pintype "bidirectional"))
      (node (ref "U$1") (pin "P$82") (pinfunction "VSS_PAD_P$82") (pintype "bidirectional"))
      (node (ref "U$1") (pin "P$83") (pinfunction "VSS_PAD_P$83") (pintype "bidirectional"))
      (node (ref "U$1") (pin "P$84") (pinfunction "VSS_PAD_P$84") (pintype "bidirectional"))
      (node (ref "U$1") (pin "P$85") (pinfunction "VSS_PAD_P$85") (pintype "bidirectional"))
      (node (ref "U$1") (pin "P$86") (pinfunction "VSS_PAD_P$86") (pintype "bidirectional"))
      (node (ref "U$1") (pin "P$87") (pinfunction "VSS_PAD_P$87") (pintype "bidirectional"))
      (node (ref "U$1") (pin "P$88") (pinfunction "VSS_PAD_P$88") (pintype "bidirectional"))
      (node (ref "U$1") (pin "P$89") (pinfunction "VSS_PAD_P$89") (pintype "bidirectional"))
      (node (ref "U$1") (pin "P$90") (pinfunction "VSS_PAD_P$90") (pintype "bidirectional"))
      (node (ref "U$1") (pin "P$B7") (pinfunction "VSS_P$B7") (pintype "power_in"))
      (node (ref "U$1") (pin "P$F23") (pinfunction "VSS_PA_P$F23") (pintype "bidirectional"))
      (node (ref "U3") (pin "1") (pinfunction "CTG_1") (pintype "power_in"))
      (node (ref "U3") (pin "4") (pinfunction "GND_4") (pintype "power_in"))
      (node (ref "U3") (pin "6") (pinfunction "QSTRT_6") (pintype "input"))
      (node (ref "U3") (pin "9") (pinfunction "EP_9") (pintype "power_in"))
      (node (ref "X1") (pin "2") (pinfunction "2_2") (pintype "passive"))
      (node (ref "X1") (pin "4") (pinfunction "4_4") (pintype "passive"))
    )
    (net (code "27") (name "HAPTIC_EN{slash}1.4C") (class "Default")
      (node (ref "IC2") (pin "A1") (pinfunction "EN_A1") (pintype "bidirectional"))
    )
    (net (code "28") (name "HAPTIC_EN{slash}2.6A") (class "Default")
      (node (ref "U$1") (pin "P$U1") (pinfunction "P0.12_P$U1") (pintype "bidirectional"))
    )
    (net (code "29") (name "IMU_INT1") (class "Default")
      (node (ref "IC3") (pin "5") (pinfunction "INT1_5") (pintype "bidirectional"))
      (node (ref "U$1") (pin "P$N1") (pinfunction "P0.08_P$N1") (pintype "bidirectional"))
    )
    (net (code "30") (name "IMU_INT2") (class "Default")
      (node (ref "IC3") (pin "6") (pinfunction "INT2_6") (pintype "bidirectional"))
      (node (ref "U$1") (pin "P$P2") (pinfunction "P1.08_P$P2") (pintype "bidirectional"))
    )
    (net (code "31") (name "LX1") (class "Default")
      (node (ref "IC9") (pin "B2") (pinfunction "SW1_1_B2") (pintype "bidirectional"))
      (node (ref "IC9") (pin "B3") (pinfunction "SW1_2_B3") (pintype "bidirectional"))
      (node (ref "L7") (pin "1") (pinfunction "1_1") (pintype "bidirectional"))
    )
    (net (code "32") (name "LX2") (class "Default")
      (node (ref "IC9") (pin "D2") (pinfunction "SW2_1_D2") (pintype "bidirectional"))
      (node (ref "IC9") (pin "D3") (pinfunction "SW2_2_D3") (pintype "bidirectional"))
      (node (ref "L7") (pin "2") (pinfunction "2_2") (pintype "bidirectional"))
    )
    (net (code "33") (name "MOSI{slash}1.5B") (class "Default")
      (node (ref "J1") (pin "14") (pinfunction "14_14") (pintype "bidirectional"))
    )
    (net (code "34") (name "MOSI{slash}2.2D") (class "Default")
      (node (ref "U$1") (pin "P$B13") (pinfunction "P0.03/AIN1_P$B13") (pintype "bidirectional"))
    )
    (net (code "35") (name "Net-(D2-K)") (class "Default")
      (node (ref "C2-EP-DR") (pin "1") (pinfunction "1_1") (pintype "passive"))
      (node (ref "D2") (pin "1") (pinfunction "K_1") (pintype "bidirectional"))
      (node (ref "D4") (pin "2") (pinfunction "A_2") (pintype "bidirectional"))
    )
    (net (code "36") (name "Net-(D5-A)") (class "Default")
      (node (ref "C2-EP-DR") (pin "2") (pinfunction "2_2") (pintype "passive"))
      (node (ref "D5") (pin "2") (pinfunction "A_2") (pintype "bidirectional"))
      (node (ref "L5") (pin "2") (pinfunction "2_2") (pintype "passive"))
      (node (ref "Q3") (pin "3") (pinfunction "D_3") (pintype "bidirectional"))
    )
    (net (code "37") (name "Net-(EPD_C1-Pad1)") (class "Default")
      (node (ref "EPD_C1") (pin "1") (pinfunction "1_1") (pintype "passive"))
      (node (ref "J1") (pin "5") (pinfunction "5_5") (pintype "bidirectional"))
    )
    (net (code "38") (name "Net-(EPD_C2-Pad1)") (class "Default")
      (node (ref "EPD_C2") (pin "1") (pinfunction "1_1") (pintype "passive"))
      (node (ref "J1") (pin "4") (pinfunction "4_4") (pintype "bidirectional"))
    )
    (net (code "39") (name "Net-(EPD_C6-Pad1)") (class "Default")
      (node (ref "EPD_C6") (pin "1") (pinfunction "1_1") (pintype "passive"))
      (node (ref "J1") (pin "18") (pinfunction "18_18") (pintype "bidirectional"))
    )
    (net (code "40") (name "Net-(EPD_C7-Pad1)") (class "Default")
      (node (ref "EPD_C7") (pin "1") (pinfunction "1_1") (pintype "passive"))
      (node (ref "J1") (pin "19") (pinfunction "19_19") (pintype "bidirectional"))
    )
    (net (code "41") (name "Net-(EPD_C8-Pad1)") (class "Default")
      (node (ref "EPD_C8") (pin "1") (pinfunction "1_1") (pintype "passive"))
      (node (ref "J1") (pin "20") (pinfunction "20_20") (pintype "bidirectional"))
    )
    (net (code "42") (name "Net-(EPD_C10-Pad1)") (class "Default")
      (node (ref "EPD_C10") (pin "1") (pinfunction "1_1") (pintype "passive"))
      (node (ref "J1") (pin "22") (pinfunction "22_22") (pintype "bidirectional"))
    )
    (net (code "43") (name "Net-(EPD_C12-Pad1)") (class "Default")
      (node (ref "EPD_C12") (pin "1") (pinfunction "1_1") (pintype "passive"))
      (node (ref "J1") (pin "24") (pinfunction "24_24") (pintype "bidirectional"))
    )
    (net (code "44") (name "Net-(IC1-TS{slash}MR)") (class "Default")
      (node (ref "IC1") (pin "D1") (pinfunction "TS/MR_D1") (pintype "bidirectional"))
      (node (ref "R9") (pin "2") (pinfunction "2_2") (pintype "bidirectional"))
    )
    (net (code "45") (name "Net-(IC2-REG)") (class "Default")
      (node (ref "C32") (pin "2") (pinfunction "2_2") (pintype "passive"))
      (node (ref "IC2") (pin "A2") (pinfunction "REG_A2") (pintype "bidirectional"))
    )
    (net (code "46") (name "Net-(IC3-SDO)") (class "Default")
      (node (ref "IC3") (pin "1") (pinfunction "SDO_1") (pintype "bidirectional"))
      (node (ref "R3") (pin "2") (pinfunction "2_2") (pintype "bidirectional"))
    )
    (net (code "47") (name "Net-(IC9-SCL)") (class "Default")
      (node (ref "IC9") (pin "D1") (pinfunction "SCL_D1") (pintype "bidirectional"))
      (node (ref "R4") (pin "2") (pinfunction "2_2") (pintype "bidirectional"))
    )
    (net (code "48") (name "Net-(IC9-SDA)") (class "Default")
      (node (ref "IC9") (pin "E1") (pinfunction "SDA_E1") (pintype "bidirectional"))
      (node (ref "R2") (pin "2") (pinfunction "2_2") (pintype "bidirectional"))
    )
    (net (code "49") (name "Net-(J4-CC1)") (class "Default")
      (node (ref "J4") (pin "A5") (pinfunction "CC1_A5") (pintype "bidirectional"))
      (node (ref "R1_USB") (pin "2") (pinfunction "2_2") (pintype "bidirectional"))
    )
    (net (code "50") (name "Net-(J4-CC2)") (class "Default")
      (node (ref "J4") (pin "B5") (pinfunction "CC2_B5") (pintype "bidirectional"))
      (node (ref "R2_USB") (pin "1") (pinfunction "1_1") (pintype "bidirectional"))
    )
    (net (code "51") (name "Net-(L2-Pad2)") (class "Default")
      (node (ref "L2") (pin "2") (pinfunction "2_2") (pintype "passive"))
      (node (ref "L3") (pin "1") (pinfunction "1_1") (pintype "passive"))
    )
    (net (code "52") (name "Net-(R1_EP_DR-Pad1)") (class "Default")
      (node (ref "R1_EP_DR") (pin "1") (pinfunction "1_1") (pintype "bidirectional"))
      (node (ref "R_TYPE_SEL") (pin "2") (pinfunction "2_2") (pintype "bidirectional"))
      (node (ref "SJ1") (pin "2") (pinfunction "2_2") (pintype "passive"))
    )
    (net (code "53") (name "Net-(U$1-ANT)") (class "Default")
      (node (ref "C3") (pin "1") (pinfunction "1_1") (pintype "passive"))
      (node (ref "L1") (pin "1") (pinfunction "1_1") (pintype "passive"))
      (node (ref "U$1") (pin "P$H23") (pinfunction "ANT_P$H23") (pintype "bidirectional"))
    )
    (net (code "54") (name "Net-(U$1-DCC)") (class "Default")
      (node (ref "L2") (pin "1") (pinfunction "1_1") (pintype "passive"))
      (node (ref "U$1") (pin "P$B3") (pinfunction "DCC_P$B3") (pintype "output"))
    )
    (net (code "55") (name "Net-(U$1-DEC2)") (class "Default")
      (node (ref "C13") (pin "1") (pinfunction "1_1") (pintype "passive"))
      (node (ref "U$1") (pin "P$A18") (pinfunction "DEC2_P$A18") (pintype "bidirectional"))
    )
    (net (code "56") (name "Net-(U$1-DEC3V3)") (class "Default")
      (node (ref "C20") (pin "1") (pinfunction "1_1") (pintype "passive"))
      (node (ref "U$1") (pin "P$AC5") (pinfunction "DEC3V3_P$AC5") (pintype "bidirectional"))
    )
    (net (code "57") (name "Net-(U$1-DEC5)") (class "Default")
      (node (ref "C9") (pin "1") (pinfunction "1_1") (pintype "passive"))
      (node (ref "U$1") (pin "P$N24") (pinfunction "DEC5_P$N24") (pintype "bidirectional"))
    )
    (net (code "58") (name "Net-(U$1-XC1)") (class "Default")
      (node (ref "C1") (pin "1") (pinfunction "1_1") (pintype "passive"))
      (node (ref "U$1") (pin "P$B24") (pinfunction "XC1_P$B24") (pintype "input"))
      (node (ref "X1") (pin "1") (pinfunction "1_1") (pintype "passive"))
    )
    (net (code "59") (name "Net-(U$1-XC2)") (class "Default")
      (node (ref "C2") (pin "1") (pinfunction "1_1") (pintype "passive"))
      (node (ref "U$1") (pin "P$A23") (pinfunction "XC2_P$A23") (pintype "output"))
      (node (ref "X1") (pin "3") (pinfunction "3_3") (pintype "passive"))
    )
    (net (code "60") (name "OUT+") (class "Default")
      (node (ref "IC2") (pin "A3") (pinfunction "OUT+_A3") (pintype "bidirectional"))
      (node (ref "TP_OP") (pin "TP") (pinfunction "TP_TP") (pintype "input"))
    )
    (net (code "61") (name "OUT-") (class "Default")
      (node (ref "IC2") (pin "C3") (pinfunction "OUT-_C3") (pintype "bidirectional"))
      (node (ref "TP_ON") (pin "TP") (pinfunction "TP_TP") (pintype "input"))
    )
    (net (code "62") (name "P0.04") (class "Default")
      (node (ref "U$1") (pin "P$J1") (pinfunction "P0.04/AIN2_P$J1") (pintype "bidirectional"))
    )
    (net (code "63") (name "P0.09") (class "Default")
      (node (ref "U$1") (pin "P$L24") (pinfunction "P0.09/NFC1_P$L24") (pintype "bidirectional"))
    )
    (net (code "64") (name "P0.13{slash}1.5D") (class "Default")
      (node (ref "C30") (pin "2") (pinfunction "2_2") (pintype "passive"))
      (node (ref "R5") (pin "1") (pinfunction "1_1") (pintype "bidirectional"))
      (node (ref "SW_UP") (pin "2") (pinfunction "2_2") (pintype "passive"))
    )
    (net (code "65") (name "P0.13{slash}2.6C") (class "Default")
      (node (ref "U$1") (pin "P$AD8") (pinfunction "P0.13_P$AD8") (pintype "bidirectional"))
    )
    (net (code "66") (name "P0.14{slash}1.5D") (class "Default")
      (node (ref "C31") (pin "2") (pinfunction "2_2") (pintype "passive"))
      (node (ref "R8") (pin "1") (pinfunction "1_1") (pintype "bidirectional"))
      (node (ref "SW_ENT") (pin "2") (pinfunction "2_2") (pintype "passive"))
    )
    (net (code "67") (name "P0.14{slash}2.7C") (class "Default")
      (node (ref "U$1") (pin "P$AC9") (pinfunction "P0.14_P$AC9") (pintype "bidirectional"))
    )
    (net (code "68") (name "P0.19") (class "Default")
      (node (ref "U$1") (pin "P$AC15") (pinfunction "P0.19_P$AC15") (pintype "bidirectional"))
    )
    (net (code "69") (name "P0.20") (class "Default")
      (node (ref "U$1") (pin "P$AD16") (pinfunction "P0.20_P$AD16") (pintype "bidirectional"))
    )
    (net (code "70") (name "P0.21") (class "Default")
      (node (ref "U$1") (pin "P$AC17") (pinfunction "P0.21_P$AC17") (pintype "bidirectional"))
    )
    (net (code "71") (name "P0.22") (class "Default")
      (node (ref "U$1") (pin "P$AD18") (pinfunction "P0.22_P$AD18") (pintype "bidirectional"))
    )
    (net (code "72") (name "P0.23") (class "Default")
      (node (ref "U$1") (pin "P$AC19") (pinfunction "P0.23_P$AC19") (pintype "bidirectional"))
    )
    (net (code "73") (name "P0.24") (class "Default")
      (node (ref "U$1") (pin "P$AD20") (pinfunction "P0.24_P$AD20") (pintype "bidirectional"))
    )
    (net (code "74") (name "P0.25") (class "Default")
      (node (ref "U$1") (pin "P$AC21") (pinfunction "P0.25_P$AC21") (pintype "bidirectional"))
    )
    (net (code "75") (name "P0.26") (class "Default")
      (node (ref "U$1") (pin "P$G1") (pinfunction "P0.26_P$G1") (pintype "bidirectional"))
    )
    (net (code "76") (name "P0.27") (class "Default")
      (node (ref "U$1") (pin "P$H2") (pinfunction "P0.27_P$H2") (pintype "bidirectional"))
    )
    (net (code "77") (name "P0.28") (class "Default")
      (node (ref "U$1") (pin "P$B11") (pinfunction "P0.28/AIN4_P$B11") (pintype "bidirectional"))
    )
    (net (code "78") (name "P0.29") (class "Default")
      (node (ref "U$1") (pin "P$A10") (pinfunction "P0.29/AIN5_P$A10") (pintype "bidirectional"))
    )
    (net (code "79") (name "P0.30") (class "Default")
      (node (ref "U$1") (pin "P$B9") (pinfunction "P0.30/AIN6_P$B9") (pintype "bidirectional"))
    )
    (net (code "80") (name "P0.31") (class "Default")
      (node (ref "U$1") (pin "P$A8") (pinfunction "P0.31/AIN7_P$A8") (pintype "bidirectional"))
    )
    (net (code "81") (name "P1.01{slash}1.6C") (class "Default")
      (node (ref "Q1") (pin "1") (pinfunction "G_1") (pintype "bidirectional"))
      (node (ref "R_PWR_EPD") (pin "1") (pinfunction "1_1") (pintype "bidirectional"))
    )
    (net (code "82") (name "P1.01{slash}2.4B") (class "Default")
      (node (ref "U$1") (pin "P$Y23") (pinfunction "P1.01_P$Y23") (pintype "bidirectional"))
    )
    (net (code "83") (name "P1.02{slash}1.6C") (class "Default")
      (node (ref "C29") (pin "2") (pinfunction "2_2") (pintype "passive"))
      (node (ref "R7") (pin "1") (pinfunction "1_1") (pintype "bidirectional"))
      (node (ref "SW_DN") (pin "2") (pinfunction "2_2") (pintype "passive"))
    )
    (net (code "84") (name "P1.02{slash}2.8C") (class "Default")
      (node (ref "U$1") (pin "P$W24") (pinfunction "P1.02_P$W24") (pintype "bidirectional"))
    )
    (net (code "85") (name "P1.03") (class "Default")
      (node (ref "U$1") (pin "P$V23") (pinfunction "P1.03_P$V23") (pintype "bidirectional"))
    )
    (net (code "86") (name "P1.04") (class "Default")
      (node (ref "U$1") (pin "P$U24") (pinfunction "P1.04_P$U24") (pintype "bidirectional"))
    )
    (net (code "87") (name "P1.05") (class "Default")
      (node (ref "U$1") (pin "P$T23") (pinfunction "P1.05_P$T23") (pintype "bidirectional"))
    )
    (net (code "88") (name "P1.06") (class "Default")
      (node (ref "U$1") (pin "P$R24") (pinfunction "P1.06_P$R24") (pintype "bidirectional"))
    )
    (net (code "89") (name "P1.07") (class "Default")
      (node (ref "U$1") (pin "P$P23") (pinfunction "P1.07_P$P23") (pintype "bidirectional"))
    )
    (net (code "90") (name "P1.09") (class "Default")
      (node (ref "U$1") (pin "P$R1") (pinfunction "P1.09_P$R1") (pintype "bidirectional"))
    )
    (net (code "91") (name "P1.10") (class "Default")
      (node (ref "U$1") (pin "P$A20") (pinfunction "P1.10_P$A20") (pintype "bidirectional"))
    )
    (net (code "92") (name "P1.11") (class "Default")
      (node (ref "U$1") (pin "P$B19") (pinfunction "P1.11_P$B19") (pintype "bidirectional"))
    )
    (net (code "93") (name "P1.12") (class "Default")
      (node (ref "U$1") (pin "P$B17") (pinfunction "P1.12_P$B17") (pintype "bidirectional"))
    )
    (net (code "94") (name "P1.13") (class "Default")
      (node (ref "U$1") (pin "P$A16") (pinfunction "P1.13_P$A16") (pintype "bidirectional"))
    )
    (net (code "95") (name "P1.14") (class "Default")
      (node (ref "U$1") (pin "P$B15") (pinfunction "P1.14_P$B15") (pintype "bidirectional"))
    )
    (net (code "96") (name "P1.15") (class "Default")
      (node (ref "U$1") (pin "P$A14") (pinfunction "P1.15_P$A14") (pintype "bidirectional"))
    )
    (net (code "97") (name "PMIC_INT") (class "Default")
      (node (ref "IC1") (pin "A1") (pinfunction "~{INT}_A1") (pintype "bidirectional"))
      (node (ref "U$1") (pin "P$T2") (pinfunction "P0.11_P$T2") (pintype "bidirectional"))
    )
    (net (code "98") (name "PREVGH") (class "Default")
      (node (ref "D5") (pin "1") (pinfunction "K_1") (pintype "bidirectional"))
      (node (ref "EPD_C9") (pin "1") (pinfunction "1_1") (pintype "passive"))
      (node (ref "J1") (pin "21") (pinfunction "21_21") (pintype "bidirectional"))
    )
    (net (code "99") (name "PREVGL") (class "Default")
      (node (ref "D2") (pin "2") (pinfunction "A_2") (pintype "bidirectional"))
      (node (ref "EPD_C11") (pin "1") (pinfunction "1_1") (pintype "passive"))
      (node (ref "J1") (pin "23") (pinfunction "23_23") (pintype "bidirectional"))
    )
    (net (code "100") (name "RESE") (class "Default")
      (node (ref "J1") (pin "3") (pinfunction "3_3") (pintype "bidirectional"))
      (node (ref "Q3") (pin "2") (pinfunction "S_2") (pintype "bidirectional"))
      (node (ref "R1_EP_DR") (pin "2") (pinfunction "2_2") (pintype "bidirectional"))
    )
    (net (code "101") (name "RESET") (class "Default")
      (node (ref "J2") (pin "6") (pinfunction "6_6") (pintype "bidirectional"))
      (node (ref "TP_RESET") (pin "TP") (pinfunction "TP_TP") (pintype "input"))
      (node (ref "U$1") (pin "P$AC13") (pinfunction "P0.18/RESET_P$AC13") (pintype "bidirectional"))
    )
    (net (code "102") (name "SCK{slash}1.5B") (class "Default")
      (node (ref "J1") (pin "13") (pinfunction "13_13") (pintype "bidirectional"))
    )
    (net (code "103") (name "SCK{slash}2.2D") (class "Default")
      (node (ref "U$1") (pin "P$A12") (pinfunction "P0.02/AIN0_P$A12") (pintype "bidirectional"))
    )
    (net (code "104") (name "SCL{slash}1.4C") (class "Default")
      (node (ref "IC2") (pin "C1") (pinfunction "SCL_C1") (pintype "bidirectional"))
      (node (ref "U3") (pin "7") (pinfunction "SCL_7") (pintype "input"))
    )
    (net (code "105") (name "SCL{slash}2.4C") (class "Default")
      (node (ref "IC1") (pin "B1") (pinfunction "SCL_B1") (pintype "bidirectional"))
      (node (ref "IC3") (pin "12") (pinfunction "SCX_12") (pintype "bidirectional"))
      (node (ref "R17") (pin "2") (pinfunction "2_2") (pintype "bidirectional"))
      (node (ref "R4") (pin "1") (pinfunction "1_1") (pintype "bidirectional"))
      (node (ref "TP_SCL") (pin "TP") (pinfunction "TP_TP") (pintype "input"))
      (node (ref "U$1") (pin "P$M2") (pinfunction "P0.07_P$M2") (pintype "bidirectional"))
    )
    (net (code "106") (name "SDA{slash}1.4C") (class "Default")
      (node (ref "IC2") (pin "B2") (pinfunction "SDA_B2") (pintype "bidirectional"))
      (node (ref "U3") (pin "8") (pinfunction "SDA_8") (pintype "bidirectional"))
    )
    (net (code "107") (name "SDA{slash}2.4C") (class "Default")
      (node (ref "IC1") (pin "C1") (pinfunction "SDA_C1") (pintype "bidirectional"))
      (node (ref "IC3") (pin "2") (pinfunction "SDX_2") (pintype "bidirectional"))
      (node (ref "R18") (pin "2") (pinfunction "2_2") (pintype "bidirectional"))
      (node (ref "R2") (pin "1") (pinfunction "1_1") (pintype "bidirectional"))
      (node (ref "TP_SDA") (pin "TP") (pinfunction "TP_TP") (pintype "input"))
      (node (ref "U$1") (pin "P$L1") (pinfunction "P0.06_P$L1") (pintype "bidirectional"))
    )
    (net (code "108") (name "SWDCLK") (class "Default")
      (node (ref "J2") (pin "4") (pinfunction "4_4") (pintype "bidirectional"))
      (node (ref "TP_SWDCLK") (pin "TP") (pinfunction "TP_TP") (pintype "input"))
      (node (ref "U$1") (pin "P$AA24") (pinfunction "SWDCLK_P$AA24") (pintype "input"))
    )
    (net (code "109") (name "SWDIO") (class "Default")
      (node (ref "J2") (pin "2") (pinfunction "2_2") (pintype "bidirectional"))
      (node (ref "TP_SWDIO") (pin "TP") (pinfunction "TP_TP") (pintype "input"))
      (node (ref "U$1") (pin "P$AC24") (pinfunction "SWDIO_P$AC24") (pintype "bidirectional"))
    )
    (net (code "110") (name "SWO") (class "Default")
      (node (ref "TP_SWO") (pin "TP") (pinfunction "TP_TP") (pintype "input"))
      (node (ref "U$1") (pin "P$AD22") (pinfunction "P1.00_P$AD22") (pintype "bidirectional"))
    )
    (net (code "111") (name "VBAT{slash}1.2A") (class "Default")
      (node (ref "C27") (pin "2") (pinfunction "2_2") (pintype "passive"))
      (node (ref "TP_VBAT") (pin "TP") (pinfunction "TP_TP") (pintype "input"))
      (node (ref "U3") (pin "2") (pinfunction "CELL_2") (pintype "power_in"))
      (node (ref "U3") (pin "3") (pinfunction "VDD_3") (pintype "power_in"))
    )
    (net (code "112") (name "VBAT{slash}2.5C") (class "Default")
      (node (ref "C37") (pin "2") (pinfunction "2_2") (pintype "passive"))
      (node (ref "IC1") (pin "C2") (pinfunction "BAT_C2") (pintype "bidirectional"))
    )
    (net (code "113") (name "VBUS{slash}1.5D") (class "Default")
      (node (ref "C42") (pin "1") (pinfunction "1_1") (pintype "passive"))
      (node (ref "C43") (pin "1") (pinfunction "1_1") (pintype "passive"))
      (node (ref "D3") (pin "5") (pinfunction "VBUS_5") (pintype "bidirectional"))
      (node (ref "J4") (pin "A4_B9") (pinfunction "VBUS_A4_B9") (pintype "power_in"))
      (node (ref "J4") (pin "A9_B4") (pinfunction "VBUS_A9_B4") (pintype "power_in"))
    )
    (net (code "114") (name "VBUS{slash}2.6D") (class "Default")
      (node (ref "C21") (pin "1") (pinfunction "1_1") (pintype "passive"))
      (node (ref "C38") (pin "2") (pinfunction "2_2") (pintype "passive"))
      (node (ref "IC1") (pin "A2") (pinfunction "IN_A2") (pintype "bidirectional"))
      (node (ref "U$1") (pin "P$AD2") (pinfunction "VBUS_P$AD2") (pintype "power_in"))
    )
    (net (code "115") (name "VREG") (class "Default")
      (node (ref "C23") (pin "2") (pinfunction "2_2") (pintype "passive"))
      (node (ref "C24") (pin "1") (pinfunction "1_1") (pintype "passive"))
      (node (ref "C39") (pin "1") (pinfunction "1_1") (pintype "passive"))
      (node (ref "IC1") (pin "B2") (pinfunction "SYS_B2") (pintype "bidirectional"))
      (node (ref "IC9") (pin "A1") (pinfunction "EN_A1") (pintype "bidirectional"))
      (node (ref "IC9") (pin "A2") (pinfunction "VIN_1_A2") (pintype "bidirectional"))
      (node (ref "IC9") (pin "A3") (pinfunction "VIN_2_A3") (pintype "bidirectional"))
      (node (ref "TP_VREG") (pin "TP") (pinfunction "TP_TP") (pintype "input"))
    )
    (net (code "116") (name "unconnected-(ANT1-NC-Pad2)") (class "Default")
      (node (ref "ANT1") (pin "2") (pinfunction "NC_2") (pintype "no_connect"))
    )
    (net (code "117") (name "unconnected-(IC3-ASCL-Pad11)") (class "Default")
      (node (ref "IC3") (pin "11") (pinfunction "ASCL_11") (pintype "bidirectional"))
    )
    (net (code "118") (name "unconnected-(IC3-ASDA-Pad4)") (class "Default")
      (node (ref "IC3") (pin "4") (pinfunction "ASDA_4") (pintype "bidirectional"))
    )
    (net (code "119") (name "unconnected-(J1-Pad1)") (class "Default")
      (node (ref "J1") (pin "1") (pinfunction "1_1") (pintype "bidirectional"))
    )
    (net (code "120") (name "unconnected-(J1-Pad6)") (class "Default")
      (node (ref "J1") (pin "6") (pinfunction "6_6") (pintype "bidirectional"))
    )
    (net (code "121") (name "unconnected-(J1-Pad7)") (class "Default")
      (node (ref "J1") (pin "7") (pinfunction "7_7") (pintype "bidirectional"))
    )
    (net (code "122") (name "unconnected-(J4-SBU1-PadA8)") (class "Default")
      (node (ref "J4") (pin "A8") (pinfunction "SBU1_A8") (pintype "bidirectional"))
    )
    (net (code "123") (name "unconnected-(J4-SBU2-PadB8)") (class "Default")
      (node (ref "J4") (pin "B8") (pinfunction "SBU2_B8") (pintype "bidirectional"))
    )
    (net (code "124") (name "unconnected-(U$1-DCCH-PadP$AB2)") (class "Default")
      (node (ref "U$1") (pin "P$AB2") (pinfunction "DCCH_P$AB2") (pintype "bidirectional"))
    )
  )
)
